# Power.net
KiCad netlist of a schematic drawn in Altium Designer
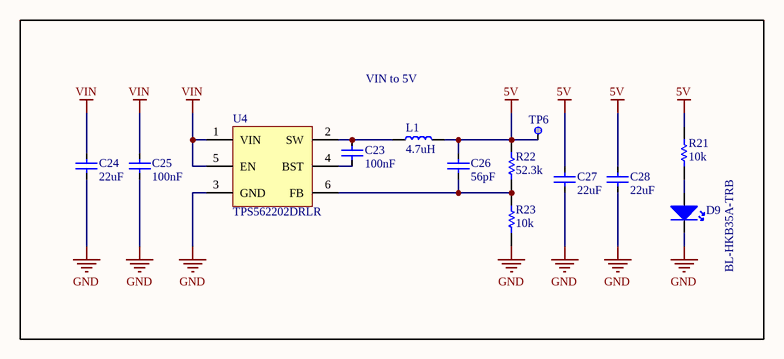
[diagram p0: Power.SchDoc]

(export (version "E")
  (design (tool "Eeschema 10.0.6"))
  (components
    (comp (ref "C23")
      (value "100nF")
      (footprint "CAP-0603")
      (fields
        (field (name "MANUFACTURER") "TDK")
        (field (name "VOLTAGE") "50V")
        (field (name "TOLERANCE") "%10")
      )
      (libsource (lib "My_Libs") (part "CGA3E2X7R1H104K080AA"))
    )
    (comp (ref "C24")
      (value "22uF")
      (footprint "CAP-1210")
      (fields
        (field (name "MANUFACTURER") "Samsung Electro-Mechanics")
        (field (name "VOLTAGE") "25V")
        (field (name "TOLERANCE") "%10")
      )
      (libsource (lib "My_Libs") (part "CL32B226KAJNNNE"))
    )
    (comp (ref "C25")
      (value "100nF")
      (footprint "CAP-0603")
      (fields
        (field (name "MANUFACTURER") "TDK")
        (field (name "VOLTAGE") "50V")
        (field (name "TOLERANCE") "%10")
      )
      (libsource (lib "My_Libs") (part "CGA3E2X7R1H104K080AA"))
    )
    (comp (ref "C26")
      (value "56pF")
      (footprint "CAP-0603")
      (fields
        (field (name "MANUFACTURER") "Murata")
        (field (name "TOLERANCE") "%1")
        (field (name "VOLTAGE") "100V")
      )
      (libsource (lib "My_Libs") (part "GCM1885C2A560FA16D"))
    )
    (comp (ref "C27")
      (value "22uF")
      (footprint "CAP-1210")
      (fields
        (field (name "MANUFACTURER") "Samsung Electro-Mechanics")
        (field (name "VOLTAGE") "25V")
        (field (name "TOLERANCE") "%10")
      )
      (libsource (lib "My_Libs") (part "CL32B226KAJNNNE"))
    )
    (comp (ref "C28")
      (value "22uF")
      (footprint "CAP-1210")
      (fields
        (field (name "MANUFACTURER") "Samsung Electro-Mechanics")
        (field (name "VOLTAGE") "25V")
        (field (name "TOLERANCE") "%10")
      )
      (libsource (lib "My_Libs") (part "CL32B226KAJNNNE"))
    )
    (comp (ref "D9")
      (value "BL-HKB35A-TRB")
      (footprint "LED-0805")
      (fields (field (name "MANUFACTURER") "BRIGHT LED"))
      (libsource (lib "My_Libs") (part "BL-HKB35A-TRB"))
    )
    (comp (ref "L1")
      (value "4.7uH")
      (footprint "IND_EATON_DR125-4R7-R")
      (fields (field (name "MANUFACTURER") "Eaton") (field (name "TOLERANCE") "%20"))
      (libsource (lib "My_Libs") (part "DR125-4R7-R"))
    )
    (comp (ref "R21")
      (value "10k")
      (footprint "RES-0603")
      (fields
        (field (name "MANUFACTURER") "Vishay")
        (field (name "TOLERANCE") "%1")
        (field (name "POWER") "0.1W")
      )
      (libsource (lib "My_Libs") (part "CRCW060310K0FKEA"))
    )
    (comp (ref "R22")
      (value "52.3k")
      (footprint "RES-0603")
      (fields
        (field (name "MANUFACTURER") "Panasonic")
        (field (name "TOLERANCE") "%1")
        (field (name "POWER") "0.1W")
      )
      (libsource (lib "My_Libs") (part "ERJ-3EKF5232V"))
    )
    (comp (ref "R23")
      (value "10k")
      (footprint "RES-0603")
      (fields
        (field (name "MANUFACTURER") "Vishay")
        (field (name "TOLERANCE") "%1")
        (field (name "POWER") "0.1W")
      )
      (libsource (lib "My_Libs") (part "CRCW060310K0FKEA"))
    )
    (comp (ref "TP6")
      (value "Test Point")
      (footprint "0.8mm Test Point")
      (libsource (lib "My_Libs") (part "Test Point"))
    )
    (comp (ref "U4")
      (value "TPS562202DRLR")
      (footprint "SOT-563")
      (fields (field (name "MANUFACTURER") "Texas Instruments"))
      (libsource (lib "My_Libs") (part "TPS562202DRLR"))
    )
  )
  (nets
    (net (code "1") (name "5V") (class "Default")
      (node (ref "C26") (pin "2") (pinfunction "2_2") (pintype "passive"))
      (node (ref "C27") (pin "2") (pinfunction "2_2") (pintype "passive"))
      (node (ref "C28") (pin "2") (pinfunction "2_2") (pintype "passive"))
      (node (ref "L1") (pin "2") (pinfunction "2_2") (pintype "passive"))
      (node (ref "R21") (pin "2") (pinfunction "2_2") (pintype "passive"))
      (node (ref "R22") (pin "2") (pinfunction "2_2") (pintype "passive"))
      (node (ref "TP6") (pin "1") (pinfunction "1_1") (pintype "passive"))
    )
    (net (code "2") (name "GND") (class "Default")
      (node (ref "C24") (pin "1") (pinfunction "1_1") (pintype "passive"))
      (node (ref "C25") (pin "1") (pinfunction "1_1") (pintype "passive"))
      (node (ref "C27") (pin "1") (pinfunction "1_1") (pintype "passive"))
      (node (ref "C28") (pin "1") (pinfunction "1_1") (pintype "passive"))
      (node (ref "D9") (pin "2") (pinfunction "K_2") (pintype "passive"))
      (node (ref "R23") (pin "1") (pinfunction "1_1") (pintype "passive"))
      (node (ref "U4") (pin "3") (pinfunction "GND_3") (pintype "passive"))
    )
    (net (code "3") (name "Net-(D9-A)") (class "Default")
      (node (ref "D9") (pin "1") (pinfunction "A_1") (pintype "passive"))
      (node (ref "R21") (pin "1") (pinfunction "1_1") (pintype "passive"))
    )
    (net (code "4") (name "Net-(U4-BST)") (class "Default")
      (node (ref "C23") (pin "1") (pinfunction "1_1") (pintype "passive"))
      (node (ref "U4") (pin "4") (pinfunction "BST_4") (pintype "passive"))
    )
    (net (code "5") (name "Net-(U4-FB)") (class "Default")
      (node (ref "C26") (pin "1") (pinfunction "1_1") (pintype "passive"))
      (node (ref "R22") (pin "1") (pinfunction "1_1") (pintype "passive"))
      (node (ref "R23") (pin "2") (pinfunction "2_2") (pintype "passive"))
      (node (ref "U4") (pin "6") (pinfunction "FB_6") (pintype "passive"))
    )
    (net (code "6") (name "Net-(U4-SW)") (class "Default")
      (node (ref "C23") (pin "2") (pinfunction "2_2") (pintype "passive"))
      (node (ref "L1") (pin "1") (pinfunction "1_1") (pintype "passive"))
      (node (ref "U4") (pin "2") (pinfunction "SW_2") (pintype "passive"))
    )
    (net (code "7") (name "VIN") (class "Default")
      (node (ref "C24") (pin "2") (pinfunction "2_2") (pintype "passive"))
      (node (ref "C25") (pin "2") (pinfunction "2_2") (pintype "passive"))
      (node (ref "U4") (pin "1") (pinfunction "VIN_1") (pintype "passive"))
      (node (ref "U4") (pin "5") (pinfunction "EN_5") (pintype "passive"))
    )
  )
)
